# muscleSensor.net
KiCad netlist of a schematic drawn in EAGLE
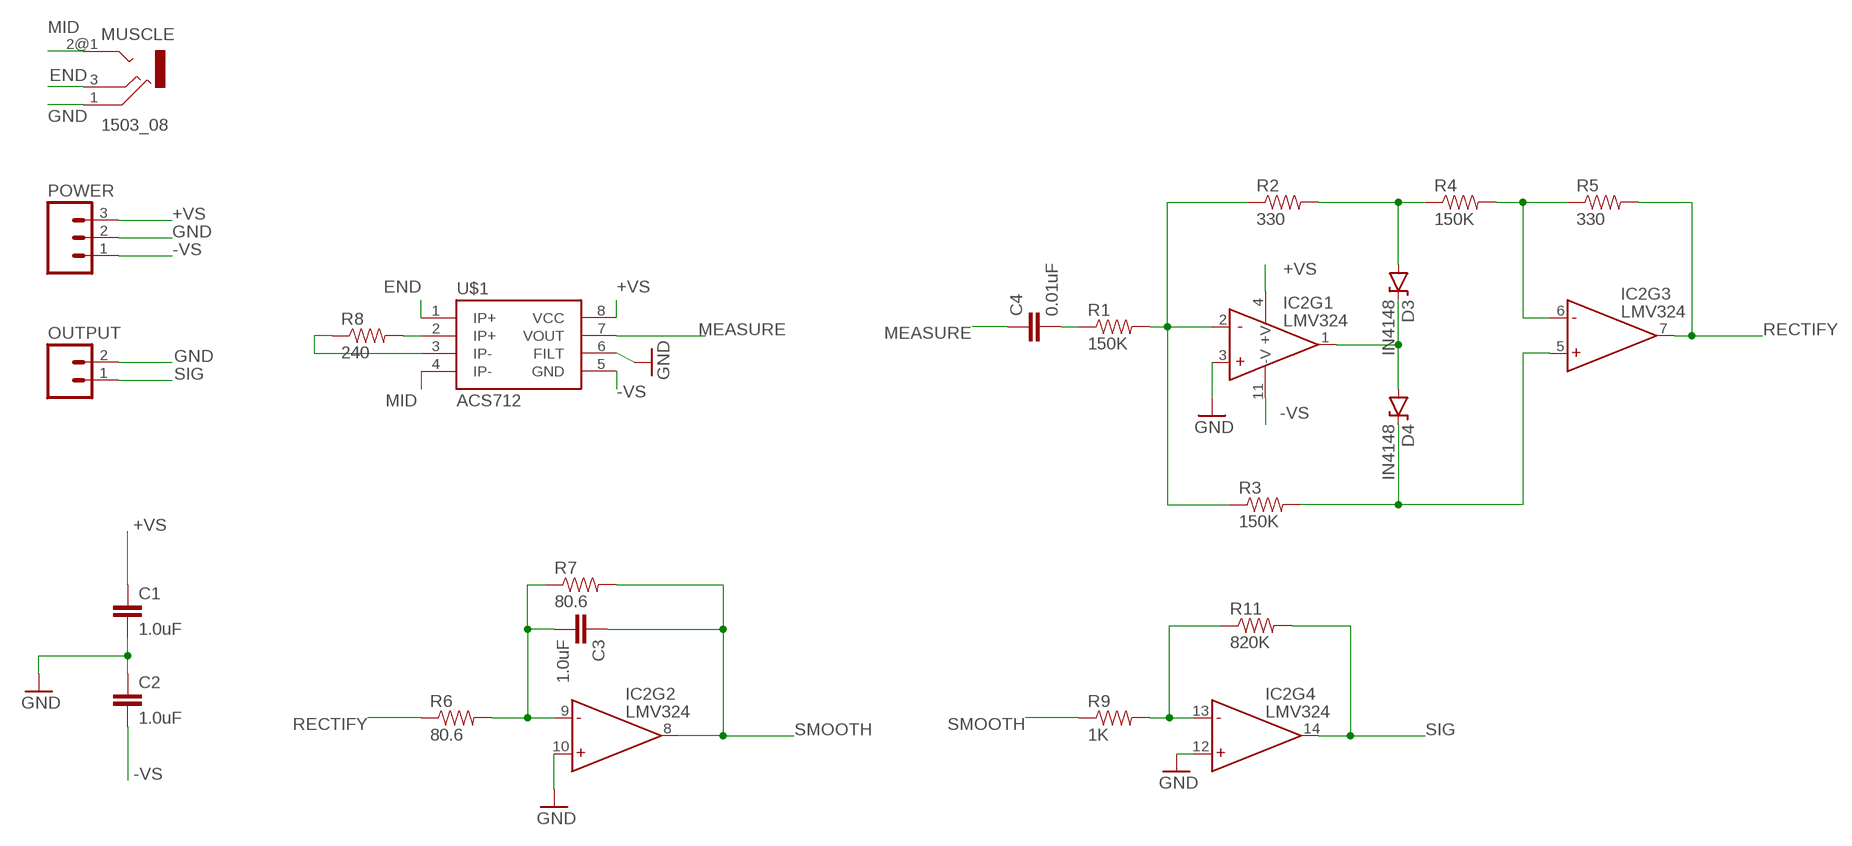
[diagram p0: schematic, sheet 1]

(export (version "E")
  (design (tool "Eeschema 10.0.6"))
  (components
    (comp (ref "C1")
      (value "1.0uF")
      (footprint "eagle-import:0603-CAP")
      (libsource (lib "eagle-import") (part "1.0UF-16V-10%(0603)"))
    )
    (comp (ref "C2")
      (value "1.0uF")
      (footprint "eagle-import:0603-CAP")
      (libsource (lib "eagle-import") (part "1.0UF-16V-10%(0603)"))
    )
    (comp (ref "C3")
      (value "1.0uF")
      (footprint "eagle-import:0603-CAP")
      (libsource (lib "eagle-import") (part "1.0UF-16V-10%(0603)"))
    )
    (comp (ref "C4")
      (value "0.01uF")
      (footprint "eagle-import:0603-CAP")
      (libsource (lib "eagle-import") (part "0.1UF-25V(+80/-20%)(0603)"))
    )
    (comp (ref "D3")
      (value "IN4148")
      (footprint "eagle-import:SOD-123")
      (libsource (lib "eagle-import") (part "DIODE-ZENER16V"))
    )
    (comp (ref "D4")
      (value "IN4148")
      (footprint "eagle-import:SOD-123")
      (libsource (lib "eagle-import") (part "DIODE-ZENER16V"))
    )
    (comp (ref "IC2")
      (value "LMV324")
      (footprint "eagle-import:SO014")
      (libsource (lib "eagle-import") (part "LMV324"))
    )
    (comp (ref "MUSCLE")
      (value "1503_08")
      (footprint "eagle-import:1503_08")
      (libsource (lib "eagle-import") (part "1503_?08"))
    )
    (comp (ref "OUTPUT")
      (value "M02LOCK_LONGPADS")
      (footprint "eagle-import:1X02_LOCK_LONGPADS")
      (libsource (lib "eagle-import") (part "M02LOCK_LONGPADS"))
    )
    (comp (ref "POWER")
      (value "M03LOCK_LONGPADS")
      (footprint "eagle-import:1X03_LOCK_LONGPADS")
      (libsource (lib "eagle-import") (part "M03LOCK_LONGPADS"))
    )
    (comp (ref "R1")
      (value "150K")
      (footprint "eagle-import:0603-RES")
      (libsource (lib "eagle-import") (part "150KOHM1/10W1%(0603)"))
    )
    (comp (ref "R2")
      (value "330")
      (footprint "eagle-import:0603-RES")
      (libsource (lib "eagle-import") (part "150KOHM1/10W1%(0603)"))
    )
    (comp (ref "R3")
      (value "150K")
      (footprint "eagle-import:0603-RES")
      (libsource (lib "eagle-import") (part "150KOHM1/10W1%(0603)"))
    )
    (comp (ref "R4")
      (value "150K")
      (footprint "eagle-import:0603-RES")
      (libsource (lib "eagle-import") (part "150KOHM1/10W1%(0603)"))
    )
    (comp (ref "R5")
      (value "330")
      (footprint "eagle-import:0603-RES")
      (libsource (lib "eagle-import") (part "150KOHM1/10W1%(0603)"))
    )
    (comp (ref "R6")
      (value "80.6")
      (footprint "eagle-import:0603-RES")
      (libsource (lib "eagle-import") (part "150KOHM1/10W1%(0603)"))
    )
    (comp (ref "R7")
      (value "80.6")
      (footprint "eagle-import:0603-RES")
      (libsource (lib "eagle-import") (part "150KOHM1/10W1%(0603)"))
    )
    (comp (ref "R8")
      (value "240")
      (footprint "eagle-import:0603-RES")
      (libsource (lib "eagle-import") (part "240OHM1/10W1%(0603)"))
    )
    (comp (ref "R9")
      (value "1K")
      (footprint "eagle-import:0603-RES")
      (libsource (lib "eagle-import") (part "1KOHM-1/10W-1%(0603)"))
    )
    (comp (ref "R11")
      (value "820K")
      (footprint "eagle-import:0603-RES")
      (libsource (lib "eagle-import") (part "150KOHM1/10W1%(0603)"))
    )
    (comp (ref "U$1")
      (value "ACS712")
      (footprint "eagle-import:SO08")
      (libsource (lib "eagle-import") (part "ACS712"))
    )
  )
  (nets
    (net (code "1") (name "/+VS") (class "Default")
      (node (ref "C1") (pin "1") (pinfunction "1_1") (pintype "passive"))
      (node (ref "IC2") (pin "4") (pinfunction "+V_4") (pintype "power_in"))
      (node (ref "POWER") (pin "3") (pinfunction "3_3") (pintype "passive"))
      (node (ref "U$1") (pin "8") (pinfunction "VCC_8") (pintype "bidirectional"))
    )
    (net (code "2") (name "/-VS") (class "Default")
      (node (ref "C2") (pin "2") (pinfunction "2_2") (pintype "passive"))
      (node (ref "IC2") (pin "11") (pinfunction "-V_11") (pintype "power_in"))
      (node (ref "POWER") (pin "1") (pinfunction "1_1") (pintype "passive"))
      (node (ref "U$1") (pin "5") (pinfunction "GND_5") (pintype "bidirectional"))
    )
    (net (code "3") (name "/END") (class "Default")
      (node (ref "MUSCLE") (pin "3") (pinfunction "3_3") (pintype "passive"))
      (node (ref "U$1") (pin "1") (pinfunction "IP+_1") (pintype "bidirectional"))
    )
    (net (code "4") (name "/MEASURE") (class "Default")
      (node (ref "C4") (pin "1") (pinfunction "1_1") (pintype "passive"))
      (node (ref "U$1") (pin "7") (pinfunction "VOUT_7") (pintype "bidirectional"))
    )
    (net (code "5") (name "/MID") (class "Default")
      (node (ref "MUSCLE") (pin "2@1") (pinfunction "2_2@1") (pintype "passive"))
      (node (ref "U$1") (pin "4") (pinfunction "IP-_4") (pintype "bidirectional"))
    )
    (net (code "6") (name "/RECTIFY") (class "Default")
      (node (ref "IC2") (pin "7") (pinfunction "OUT_7") (pintype "output"))
      (node (ref "R5") (pin "2") (pinfunction "2_2") (pintype "passive"))
      (node (ref "R6") (pin "1") (pinfunction "1_1") (pintype "passive"))
    )
    (net (code "7") (name "/SIG") (class "Default")
      (node (ref "IC2") (pin "14") (pinfunction "OUT_14") (pintype "output"))
      (node (ref "OUTPUT") (pin "1") (pinfunction "1_1") (pintype "passive"))
      (node (ref "R11") (pin "2") (pinfunction "2_2") (pintype "passive"))
    )
    (net (code "8") (name "/SMOOTH") (class "Default")
      (node (ref "C3") (pin "1") (pinfunction "1_1") (pintype "passive"))
      (node (ref "IC2") (pin "8") (pinfunction "OUT_8") (pintype "output"))
      (node (ref "R7") (pin "2") (pinfunction "2_2") (pintype "passive"))
      (node (ref "R9") (pin "1") (pinfunction "1_1") (pintype "passive"))
    )
    (net (code "9") (name "GND") (class "Default")
      (node (ref "C1") (pin "2") (pinfunction "2_2") (pintype "passive"))
      (node (ref "C2") (pin "1") (pinfunction "1_1") (pintype "passive"))
      (node (ref "IC2") (pin "10") (pinfunction "+IN_10") (pintype "input"))
      (node (ref "IC2") (pin "12") (pinfunction "+IN_12") (pintype "input"))
      (node (ref "IC2") (pin "3") (pinfunction "+IN_3") (pintype "input"))
      (node (ref "MUSCLE") (pin "1") (pinfunction "1_1") (pintype "passive"))
      (node (ref "OUTPUT") (pin "2") (pinfunction "2_2") (pintype "passive"))
      (node (ref "POWER") (pin "2") (pinfunction "2_2") (pintype "passive"))
      (node (ref "U$1") (pin "6") (pinfunction "FILT_6") (pintype "bidirectional"))
    )
    (net (code "10") (name "Net-(C4-Pad2)") (class "Default")
      (node (ref "C4") (pin "2") (pinfunction "2_2") (pintype "passive"))
      (node (ref "R1") (pin "1") (pinfunction "1_1") (pintype "passive"))
    )
    (net (code "11") (name "Net-(D3-PadA)") (class "Default")
      (node (ref "D3") (pin "A") (pinfunction "A_A") (pintype "passive"))
      (node (ref "R2") (pin "2") (pinfunction "2_2") (pintype "passive"))
      (node (ref "R4") (pin "1") (pinfunction "1_1") (pintype "passive"))
    )
    (net (code "12") (name "Net-(IC2A--IN)") (class "Default")
      (node (ref "IC2") (pin "2") (pinfunction "-IN_2") (pintype "input"))
      (node (ref "R1") (pin "2") (pinfunction "2_2") (pintype "passive"))
      (node (ref "R2") (pin "1") (pinfunction "1_1") (pintype "passive"))
      (node (ref "R3") (pin "1") (pinfunction "1_1") (pintype "passive"))
    )
    (net (code "13") (name "Net-(IC2A-OUT)") (class "Default")
      (node (ref "D3") (pin "C") (pinfunction "C_C") (pintype "passive"))
      (node (ref "D4") (pin "A") (pinfunction "A_A") (pintype "passive"))
      (node (ref "IC2") (pin "1") (pinfunction "OUT_1") (pintype "output"))
    )
    (net (code "14") (name "Net-(IC2B--IN)") (class "Default")
      (node (ref "C3") (pin "2") (pinfunction "2_2") (pintype "passive"))
      (node (ref "IC2") (pin "9") (pinfunction "-IN_9") (pintype "input"))
      (node (ref "R6") (pin "2") (pinfunction "2_2") (pintype "passive"))
      (node (ref "R7") (pin "1") (pinfunction "1_1") (pintype "passive"))
    )
    (net (code "15") (name "Net-(IC2C-+IN)") (class "Default")
      (node (ref "D4") (pin "C") (pinfunction "C_C") (pintype "passive"))
      (node (ref "IC2") (pin "5") (pinfunction "+IN_5") (pintype "input"))
      (node (ref "R3") (pin "2") (pinfunction "2_2") (pintype "passive"))
    )
    (net (code "16") (name "Net-(IC2C--IN)") (class "Default")
      (node (ref "IC2") (pin "6") (pinfunction "-IN_6") (pintype "input"))
      (node (ref "R4") (pin "2") (pinfunction "2_2") (pintype "passive"))
      (node (ref "R5") (pin "1") (pinfunction "1_1") (pintype "passive"))
    )
    (net (code "17") (name "Net-(IC2D--IN)") (class "Default")
      (node (ref "IC2") (pin "13") (pinfunction "-IN_13") (pintype "input"))
      (node (ref "R11") (pin "1") (pinfunction "1_1") (pintype "passive"))
      (node (ref "R9") (pin "2") (pinfunction "2_2") (pintype "passive"))
    )
    (net (code "18") (name "Net-(R8-Pad1)") (class "Default")
      (node (ref "R8") (pin "1") (pinfunction "1_1") (pintype "passive"))
      (node (ref "U$1") (pin "3") (pinfunction "IP-_3") (pintype "bidirectional"))
    )
    (net (code "19") (name "Net-(R8-Pad2)") (class "Default")
      (node (ref "R8") (pin "2") (pinfunction "2_2") (pintype "passive"))
      (node (ref "U$1") (pin "2") (pinfunction "IP+_2") (pintype "bidirectional"))
    )
    (net (code "20") (name "unconnected-(MUSCLE-2-Pad2@2)") (class "Default")
      (node (ref "MUSCLE") (pin "2@2") (pinfunction "2_2@2") (pintype "passive"))
    )
  )
)
